# DIMMER.net
KiCad netlist of a schematic drawn in EAGLE
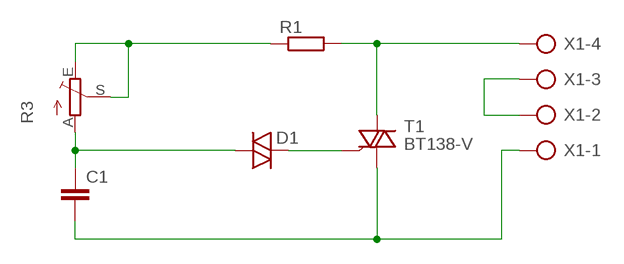
[diagram p0: schematic, sheet 1]

(export (version "E")
  (design (tool "Eeschema 10.0.6"))
  (components
    (comp (ref "C1")
      (value "C15/5")
      (footprint "eagle-import:C15B5")
      (libsource (lib "eagle-import") (part "C15/5"))
    )
    (comp (ref "D1")
      (value "DIAC-GT32")
      (footprint "eagle-import:GT32")
      (libsource (lib "eagle-import") (part "DIAC-GT32"))
    )
    (comp (ref "R1")
      (value "R-EU_0207/10")
      (footprint "eagle-import:0207_10")
      (libsource (lib "eagle-import") (part "R-EU_0207/10"))
    )
    (comp (ref "R3")
      (value "TRIM_EU-CIP20C-4MM")
      (footprint "eagle-import:CIP20C-4MM")
      (libsource (lib "eagle-import") (part "TRIM_EU-CIP20C-4MM"))
    )
    (comp (ref "T1")
      (value "BT138-V")
      (footprint "eagle-import:TO220BV")
      (libsource (lib "eagle-import") (part "BT138-V"))
    )
    (comp (ref "X1")
      (value "AK500/4")
      (footprint "eagle-import:AK500_4")
      (libsource (lib "eagle-import") (part "AK500/4"))
    )
  )
  (nets
    (net (code "1") (name "Net-(C1-Pad1)") (class "Default")
      (node (ref "C1") (pin "1") (pinfunction "1_1") (pintype "passive"))
      (node (ref "D1") (pin "1") (pinfunction "1_1") (pintype "passive"))
      (node (ref "R3") (pin "A") (pinfunction "A_A") (pintype "passive"))
    )
    (net (code "2") (name "Net-(D1-Pad2)") (class "Default")
      (node (ref "D1") (pin "2") (pinfunction "2_2") (pintype "passive"))
      (node (ref "T1") (pin "G") (pinfunction "G_G") (pintype "passive"))
    )
    (net (code "3") (name "Net-(R1-Pad1)") (class "Default")
      (node (ref "R1") (pin "1") (pinfunction "1_1") (pintype "passive"))
      (node (ref "R3") (pin "E") (pinfunction "E_E") (pintype "passive"))
      (node (ref "R3") (pin "S") (pinfunction "S_S") (pintype "passive"))
    )
    (net (code "4") (name "Net-(T1-A1)") (class "Default")
      (node (ref "C1") (pin "2") (pinfunction "2_2") (pintype "passive"))
      (node (ref "T1") (pin "T1") (pinfunction "A1_T1") (pintype "passive"))
      (node (ref "X1") (pin "1") (pinfunction "KL_1") (pintype "passive"))
    )
    (net (code "5") (name "Net-(T1-A2)") (class "Default")
      (node (ref "R1") (pin "2") (pinfunction "2_2") (pintype "passive"))
      (node (ref "T1") (pin "T2") (pinfunction "A2_T2") (pintype "passive"))
      (node (ref "X1") (pin "4") (pinfunction "KL_4") (pintype "passive"))
    )
    (net (code "6") (name "Net-(X1B-KL)") (class "Default")
      (node (ref "X1") (pin "2") (pinfunction "KL_2") (pintype "passive"))
      (node (ref "X1") (pin "3") (pinfunction "KL_3") (pintype "passive"))
    )
  )
)
